# Antenna_Board_v3.net
KiCad netlist of a schematic drawn in EAGLE
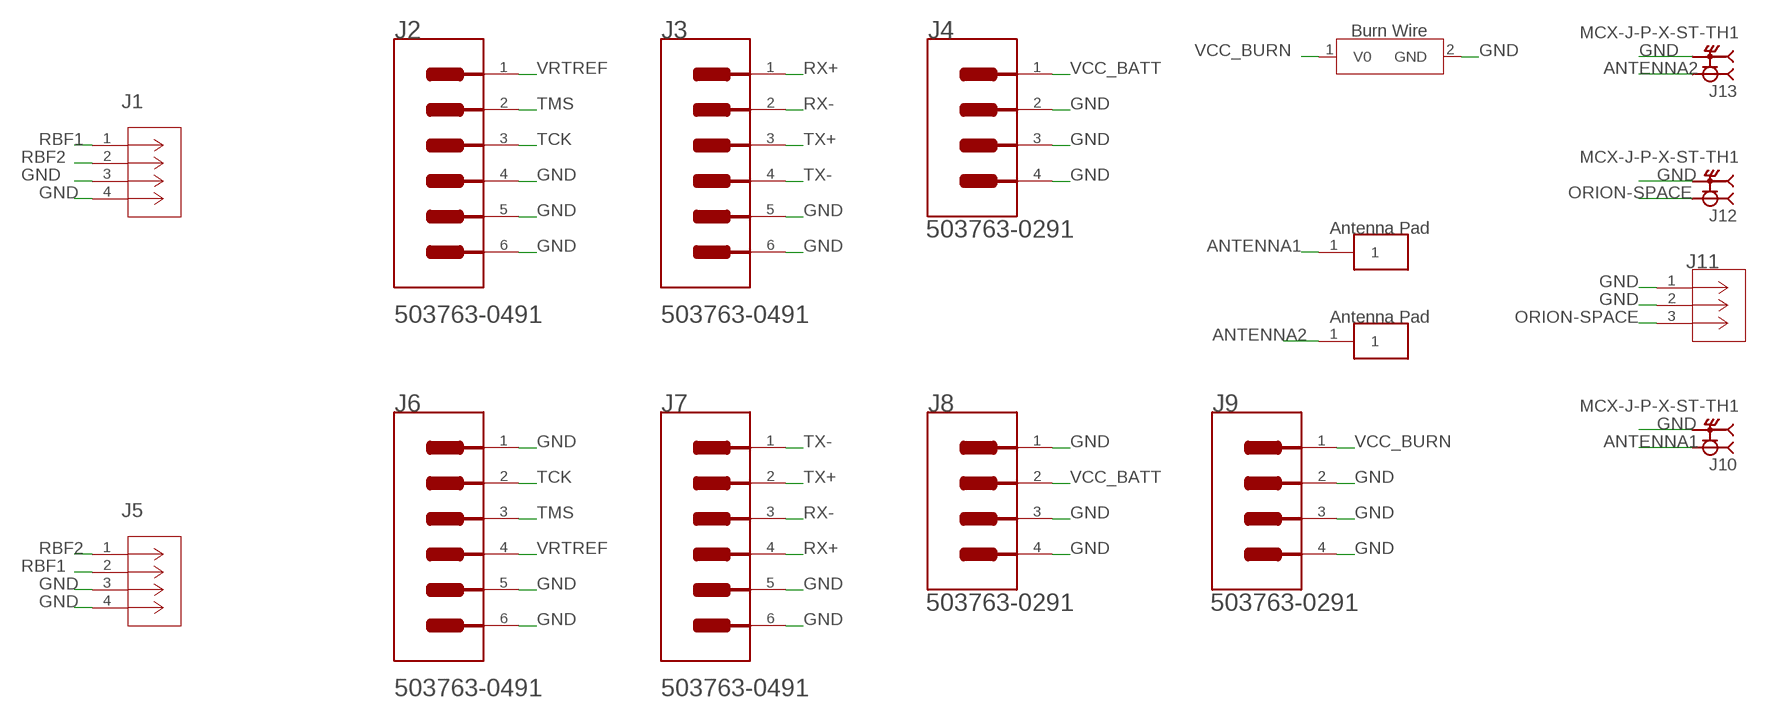
[diagram p0: schematic, sheet 1]

(export (version "E")
  (design (tool "Eeschema 10.0.6"))
  (components
    (comp (ref "J1")
      (value "5037630291")
      (footprint "eagle-import:CON_5037630291")
      (fields (field (name "COPYRIGHT") "Copyright (C) 2018 Accelerated Designs. All rights reserved"))
      (libsource (lib "eagle-import") (part "5037630291"))
    )
    (comp (ref "J2")
      (value "MOLEX_503763-0491MOLEX_503763-0491_0_0")
      (footprint "eagle-import:MOLEX_503763-0491_0")
      (fields
        (field (name "DIGIKEY_PART_NUMBER") "WM10655CT-ND")
        (field (name "MF") "Molex")
        (field (name "MOUSER_PART_NUMBER") "538-503763-0491")
      )
      (libsource (lib "eagle-import") (part "MOLEX_503763-0491MOLEX_503763-0491_0_0"))
    )
    (comp (ref "J3")
      (value "MOLEX_503763-0491MOLEX_503763-0491_0_0")
      (footprint "eagle-import:MOLEX_503763-0491_0")
      (fields
        (field (name "DIGIKEY_PART_NUMBER") "WM10655CT-ND")
        (field (name "MF") "Molex")
        (field (name "MOUSER_PART_NUMBER") "538-503763-0491")
      )
      (libsource (lib "eagle-import") (part "MOLEX_503763-0491MOLEX_503763-0491_0_0"))
    )
    (comp (ref "J4")
      (value "MOLEX_503763-0291MOLEX_503763-0291_0_0")
      (footprint "eagle-import:MOLEX_503763-0291_0")
      (fields
        (field (name "DIGIKEY_PART_NUMBER") "WM10654CT-ND")
        (field (name "MF") "Molex")
        (field (name "MOUSER_PART_NUMBER") "538-503763-0291")
      )
      (libsource (lib "eagle-import") (part "MOLEX_503763-0291MOLEX_503763-0291_0_0"))
    )
    (comp (ref "J5")
      (value "5037630291")
      (footprint "eagle-import:CON_5037630291")
      (fields (field (name "COPYRIGHT") "Copyright (C) 2018 Accelerated Designs. All rights reserved"))
      (libsource (lib "eagle-import") (part "5037630291"))
    )
    (comp (ref "J6")
      (value "MOLEX_503763-0491MOLEX_503763-0491_0_0")
      (footprint "eagle-import:MOLEX_503763-0491_0")
      (fields
        (field (name "DIGIKEY_PART_NUMBER") "WM10655CT-ND")
        (field (name "MF") "Molex")
        (field (name "MOUSER_PART_NUMBER") "538-503763-0491")
      )
      (libsource (lib "eagle-import") (part "MOLEX_503763-0491MOLEX_503763-0491_0_0"))
    )
    (comp (ref "J7")
      (value "MOLEX_503763-0491MOLEX_503763-0491_0_0")
      (footprint "eagle-import:MOLEX_503763-0491_0")
      (fields
        (field (name "DIGIKEY_PART_NUMBER") "WM10655CT-ND")
        (field (name "MF") "Molex")
        (field (name "MOUSER_PART_NUMBER") "538-503763-0491")
      )
      (libsource (lib "eagle-import") (part "MOLEX_503763-0491MOLEX_503763-0491_0_0"))
    )
    (comp (ref "J8")
      (value "MOLEX_503763-0291MOLEX_503763-0291_0_0")
      (footprint "eagle-import:MOLEX_503763-0291_0")
      (fields
        (field (name "DIGIKEY_PART_NUMBER") "WM10654CT-ND")
        (field (name "MF") "Molex")
        (field (name "MOUSER_PART_NUMBER") "538-503763-0291")
      )
      (libsource (lib "eagle-import") (part "MOLEX_503763-0291MOLEX_503763-0291_0_0"))
    )
    (comp (ref "J9")
      (value "MOLEX_503763-0291MOLEX_503763-0291_0_0")
      (footprint "eagle-import:MOLEX_503763-0291_0")
      (fields
        (field (name "DIGIKEY_PART_NUMBER") "WM10654CT-ND")
        (field (name "MF") "Molex")
        (field (name "MOUSER_PART_NUMBER") "538-503763-0291")
      )
      (libsource (lib "eagle-import") (part "MOLEX_503763-0291MOLEX_503763-0291_0_0"))
    )
    (comp (ref "J10")
      (value "MCX-J-P-X-ST-TH1")
      (footprint "eagle-import:SAMTEC_MCX-J-P-X-ST-TH1")
      (fields
        (field (name "DIGI-KEY_PART_NUMBER") "SAM8944-ND")
        (field (name "MF") "Samtec")
        (field (name "MP") "MCX-J-P-H-ST-TH1")
      )
      (libsource (lib "eagle-import") (part "MCX-J-P-X-ST-TH1"))
    )
    (comp (ref "J11")
      (value "U.FL-R-SMT-1(01)")
      (footprint "eagle-import:CONN_-SMT-1(01)")
      (fields (field (name "COPYRIGHT") "Copyright (C) 2018 Accelerated Designs. All rights reserved"))
      (libsource (lib "eagle-import") (part "U.FL-R-SMT-1(01)"))
    )
    (comp (ref "J12")
      (value "MCX-J-P-X-ST-TH1")
      (footprint "eagle-import:SAMTEC_MCX-J-P-X-ST-TH1")
      (fields
        (field (name "DIGI-KEY_PART_NUMBER") "SAM8944-ND")
        (field (name "MF") "Samtec")
        (field (name "MP") "MCX-J-P-H-ST-TH1")
      )
      (libsource (lib "eagle-import") (part "MCX-J-P-X-ST-TH1"))
    )
    (comp (ref "J13")
      (value "MCX-J-P-X-ST-TH1")
      (footprint "eagle-import:SAMTEC_MCX-J-P-X-ST-TH1")
      (fields
        (field (name "DIGI-KEY_PART_NUMBER") "SAM8944-ND")
        (field (name "MF") "Samtec")
        (field (name "MP") "MCX-J-P-H-ST-TH1")
      )
      (libsource (lib "eagle-import") (part "MCX-J-P-X-ST-TH1"))
    )
    (comp (ref "U$1")
      (value "ANTENNA_PAD")
      (footprint "eagle-import:ANTENNA_PAD")
      (libsource (lib "eagle-import") (part "ANTENNA_PAD"))
    )
    (comp (ref "U$2")
      (value "ANTENNA_PAD")
      (footprint "eagle-import:ANTENNA_PAD")
      (libsource (lib "eagle-import") (part "ANTENNA_PAD"))
    )
    (comp (ref "U$3")
      (value "BURNWIRE")
      (footprint "eagle-import:BURNWIRE")
      (libsource (lib "eagle-import") (part "BURNWIRE"))
    )
  )
  (nets
    (net (code "1") (name "/ANTENNA1") (class "Default")
      (node (ref "J10") (pin "1") (pinfunction "1_1") (pintype "passive"))
      (node (ref "U$2") (pin "1") (pinfunction "1_1") (pintype "bidirectional"))
    )
    (net (code "2") (name "/ANTENNA2") (class "Default")
      (node (ref "J13") (pin "1") (pinfunction "1_1") (pintype "passive"))
      (node (ref "U$1") (pin "1") (pinfunction "1_1") (pintype "bidirectional"))
    )
    (net (code "3") (name "/GND") (class "Default")
      (node (ref "J1") (pin "3") (pinfunction "3_3") (pintype "passive"))
      (node (ref "J1") (pin "4") (pinfunction "4_4") (pintype "passive"))
      (node (ref "J10") (pin "S1") (pinfunction "2_S1") (pintype "passive"))
      (node (ref "J10") (pin "S2") (pinfunction "2_S2") (pintype "passive"))
      (node (ref "J10") (pin "S3") (pinfunction "2_S3") (pintype "passive"))
      (node (ref "J10") (pin "S4") (pinfunction "2_S4") (pintype "passive"))
      (node (ref "J11") (pin "1") (pinfunction "1_1") (pintype "passive"))
      (node (ref "J11") (pin "2") (pinfunction "2_2") (pintype "passive"))
      (node (ref "J12") (pin "S1") (pinfunction "2_S1") (pintype "passive"))
      (node (ref "J12") (pin "S2") (pinfunction "2_S2") (pintype "passive"))
      (node (ref "J12") (pin "S3") (pinfunction "2_S3") (pintype "passive"))
      (node (ref "J12") (pin "S4") (pinfunction "2_S4") (pintype "passive"))
      (node (ref "J13") (pin "S1") (pinfunction "2_S1") (pintype "passive"))
      (node (ref "J13") (pin "S2") (pinfunction "2_S2") (pintype "passive"))
      (node (ref "J13") (pin "S3") (pinfunction "2_S3") (pintype "passive"))
      (node (ref "J13") (pin "S4") (pinfunction "2_S4") (pintype "passive"))
      (node (ref "J2") (pin "4") (pinfunction "4_4") (pintype "passive"))
      (node (ref "J2") (pin "5") (pinfunction "MNT_1_5") (pintype "passive"))
      (node (ref "J2") (pin "6") (pinfunction "MNT_2_6") (pintype "passive"))
      (node (ref "J3") (pin "5") (pinfunction "MNT_1_5") (pintype "passive"))
      (node (ref "J3") (pin "6") (pinfunction "MNT_2_6") (pintype "passive"))
      (node (ref "J4") (pin "2") (pinfunction "2_2") (pintype "bidirectional"))
      (node (ref "J4") (pin "3") (pinfunction "MNT_1_3") (pintype "bidirectional"))
      (node (ref "J4") (pin "4") (pinfunction "MNT_2_4") (pintype "bidirectional"))
      (node (ref "J5") (pin "3") (pinfunction "3_3") (pintype "passive"))
      (node (ref "J5") (pin "4") (pinfunction "4_4") (pintype "passive"))
      (node (ref "J6") (pin "1") (pinfunction "1_1") (pintype "passive"))
      (node (ref "J6") (pin "5") (pinfunction "MNT_1_5") (pintype "passive"))
      (node (ref "J6") (pin "6") (pinfunction "MNT_2_6") (pintype "passive"))
      (node (ref "J7") (pin "5") (pinfunction "MNT_1_5") (pintype "passive"))
      (node (ref "J7") (pin "6") (pinfunction "MNT_2_6") (pintype "passive"))
      (node (ref "J8") (pin "1") (pinfunction "1_1") (pintype "bidirectional"))
      (node (ref "J8") (pin "3") (pinfunction "MNT_1_3") (pintype "bidirectional"))
      (node (ref "J8") (pin "4") (pinfunction "MNT_2_4") (pintype "bidirectional"))
      (node (ref "J9") (pin "2") (pinfunction "2_2") (pintype "bidirectional"))
      (node (ref "J9") (pin "3") (pinfunction "MNT_1_3") (pintype "bidirectional"))
      (node (ref "J9") (pin "4") (pinfunction "MNT_2_4") (pintype "bidirectional"))
      (node (ref "U$3") (pin "2") (pinfunction "GND_2") (pintype "bidirectional"))
    )
    (net (code "4") (name "/ORION-SPACE") (class "Default")
      (node (ref "J11") (pin "3") (pinfunction "3_3") (pintype "passive"))
      (node (ref "J12") (pin "1") (pinfunction "1_1") (pintype "passive"))
    )
    (net (code "5") (name "/RBF1") (class "Default")
      (node (ref "J1") (pin "1") (pinfunction "1_1") (pintype "passive"))
      (node (ref "J5") (pin "2") (pinfunction "2_2") (pintype "passive"))
    )
    (net (code "6") (name "/RBF2") (class "Default")
      (node (ref "J1") (pin "2") (pinfunction "2_2") (pintype "passive"))
      (node (ref "J5") (pin "1") (pinfunction "1_1") (pintype "passive"))
    )
    (net (code "7") (name "/RX+") (class "Default")
      (node (ref "J3") (pin "1") (pinfunction "1_1") (pintype "passive"))
      (node (ref "J7") (pin "4") (pinfunction "4_4") (pintype "passive"))
    )
    (net (code "8") (name "/RX-") (class "Default")
      (node (ref "J3") (pin "2") (pinfunction "2_2") (pintype "passive"))
      (node (ref "J7") (pin "3") (pinfunction "3_3") (pintype "passive"))
    )
    (net (code "9") (name "/TCK") (class "Default")
      (node (ref "J2") (pin "3") (pinfunction "3_3") (pintype "passive"))
      (node (ref "J6") (pin "2") (pinfunction "2_2") (pintype "passive"))
    )
    (net (code "10") (name "/TMS") (class "Default")
      (node (ref "J2") (pin "2") (pinfunction "2_2") (pintype "passive"))
      (node (ref "J6") (pin "3") (pinfunction "3_3") (pintype "passive"))
    )
    (net (code "11") (name "/TX+") (class "Default")
      (node (ref "J3") (pin "3") (pinfunction "3_3") (pintype "passive"))
      (node (ref "J7") (pin "2") (pinfunction "2_2") (pintype "passive"))
    )
    (net (code "12") (name "/TX-") (class "Default")
      (node (ref "J3") (pin "4") (pinfunction "4_4") (pintype "passive"))
      (node (ref "J7") (pin "1") (pinfunction "1_1") (pintype "passive"))
    )
    (net (code "13") (name "/VCC_BATT") (class "Default")
      (node (ref "J4") (pin "1") (pinfunction "1_1") (pintype "bidirectional"))
      (node (ref "J8") (pin "2") (pinfunction "2_2") (pintype "bidirectional"))
    )
    (net (code "14") (name "/VCC_BURN") (class "Default")
      (node (ref "J9") (pin "1") (pinfunction "1_1") (pintype "bidirectional"))
      (node (ref "U$3") (pin "1") (pinfunction "V0_1") (pintype "bidirectional"))
    )
    (net (code "15") (name "/VRTREF") (class "Default")
      (node (ref "J2") (pin "1") (pinfunction "1_1") (pintype "passive"))
      (node (ref "J6") (pin "4") (pinfunction "4_4") (pintype "passive"))
    )
  )
)
